# ADC_Subsystem.net
KiCad netlist of a schematic drawn in Altium Designer
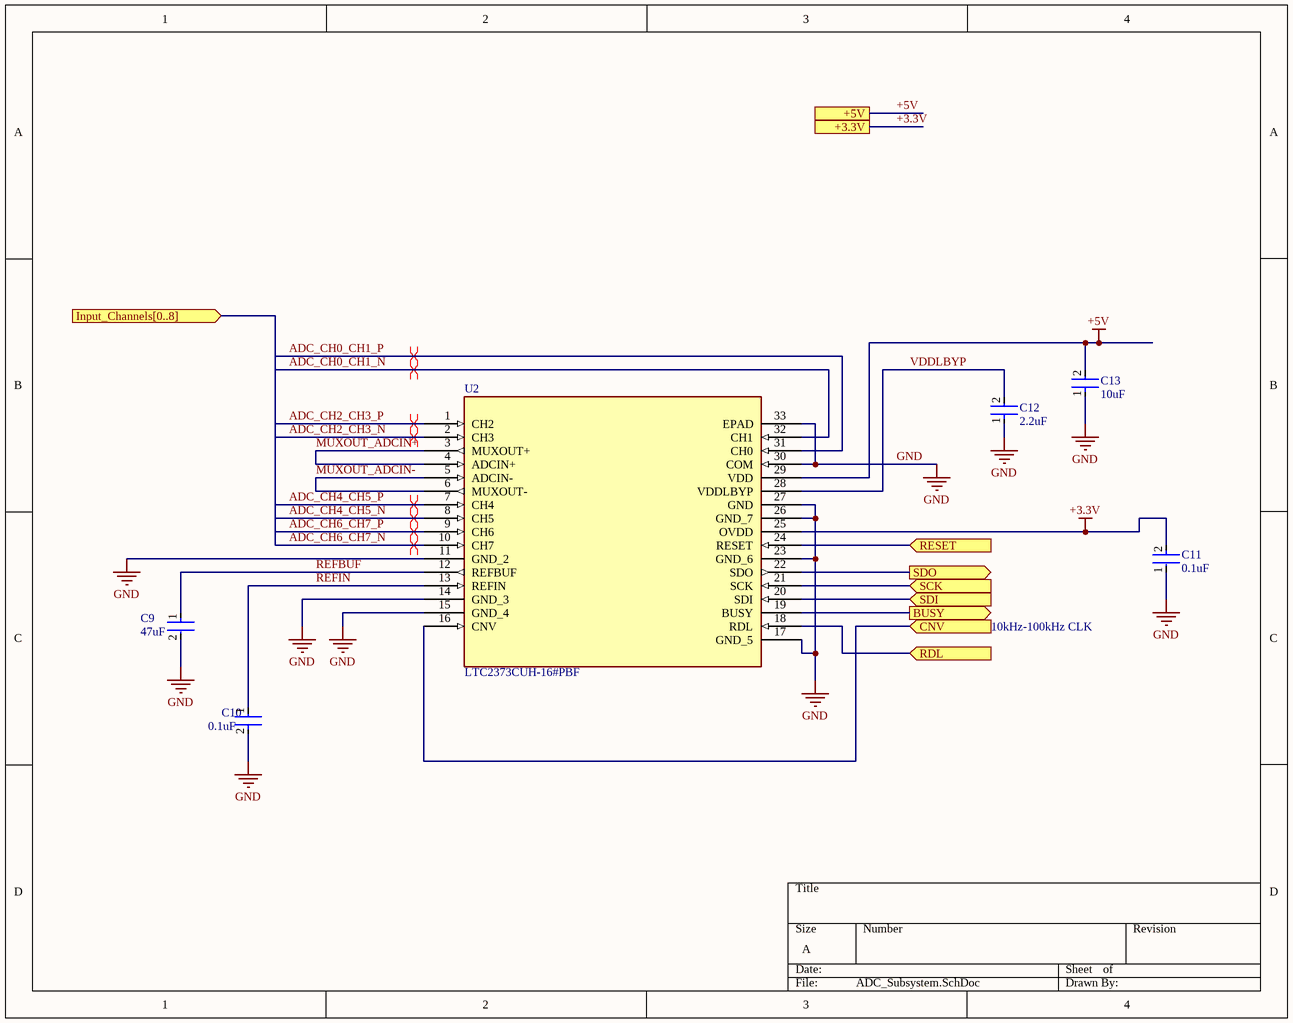
[diagram p0: ADC_Subsystem.SchDoc]

(export (version "E")
  (design (tool "Eeschema 10.0.6"))
  (components
    (comp (ref "C9")
      (value "47uF")
      (footprint "FP-C0805C476M9PACTU-MFG")
      (description "CAP CER 47UF 6.3V X5R 0805\r\nC0805C476M9PACTU")
      (fields (field (name "VOLTAGE") "6.3V") (field (name "TOLERANCE") "20%"))
      (libsource (lib "Altium Content Vault") (part "11868f565c42a9108669ba33697ecf6"))
    )
    (comp (ref "C10")
      (value "0.1uF")
      (footprint "FP-GRM15-MFG")
      (description "CAP CER 0.1UF 16V X7R 0402\r\nGRM155R71C104KA88D")
      (fields (field (name "MANUFACTURER PART NUMBER") "GRM155R71C104KA88D") (field (name "TOLERANCE") "10%"))
      (libsource (lib "Altium Content Vault") (part "236180d848d6139a670b325ea6854c9"))
    )
    (comp (ref "C11")
      (value "0.1uF")
      (footprint "FP-GRM15-MFG")
      (description "CAP CER 0.1UF 16V X7R 0402\r\nGRM155R71C104KA88D")
      (fields (field (name "MANUFACTURER PART NUMBER") "GRM155R71C104KA88D") (field (name "TOLERANCE") "10%"))
      (libsource (lib "Altium Content Vault") (part "236180d848d6139a670b325ea6854c9"))
    )
    (comp (ref "C12")
      (value "2.2uF")
      (footprint "FP-GRM188-0_1-e0_2_0_5-MFG")
      (fields (field (name "VOLTAGE") "10V") (field (name "TOLERANCE") "10%"))
      (libsource (lib "Altium Content Vault") (part "11868f565c42a9108669ba33697ecf6"))
    )
    (comp (ref "C13")
      (value "10uF")
      (footprint "FP-GRM188-0_1-e0_2_0_55-IPC_A")
      (fields (field (name "VOLTAGE") "6.3V") (field (name "TOLERANCE") "20%"))
      (libsource (lib "Altium Content Vault") (part "02cd4be3c70576c341d710602a673aa"))
    )
    (comp (ref "U2")
      (value "LTC2373CUH-16#PBF")
      (footprint "LTC_2373_Footprint")
      (libsource (lib "LTC2373CUH-16#PBF") (part "LTC2373CUH-16#PBF"))
    )
  )
  (nets
    (net (code "10") (name "+3.3V") (class "Default")
      (node (ref "C11") (pin "2") (pinfunction "2_2") (pintype "passive"))
      (node (ref "U2") (pin "25") (pinfunction "OVDD_25") (pintype "power_in"))
    )
    (net (code "11") (name "+5V") (class "Default")
      (node (ref "C13") (pin "2") (pinfunction "2_2") (pintype "passive"))
      (node (ref "U2") (pin "29") (pinfunction "VDD_29") (pintype "power_in"))
    )
    (net (code "12") (name "/ADC_CH0_CH1_N") (class "Default")
      (node (ref "U2") (pin "32") (pinfunction "CH1_32") (pintype "input"))
    )
    (net (code "13") (name "/ADC_CH0_CH1_P") (class "Default")
      (node (ref "U2") (pin "31") (pinfunction "CH0_31") (pintype "input"))
    )
    (net (code "14") (name "/ADC_CH2_CH3_N") (class "Default")
      (node (ref "U2") (pin "2") (pinfunction "CH3_2") (pintype "input"))
    )
    (net (code "15") (name "/ADC_CH2_CH3_P") (class "Default")
      (node (ref "U2") (pin "1") (pinfunction "CH2_1") (pintype "input"))
    )
    (net (code "16") (name "/ADC_CH4_CH5_N") (class "Default")
      (node (ref "U2") (pin "8") (pinfunction "CH5_8") (pintype "input"))
    )
    (net (code "17") (name "/ADC_CH4_CH5_P") (class "Default")
      (node (ref "U2") (pin "7") (pinfunction "CH4_7") (pintype "input"))
    )
    (net (code "18") (name "/ADC_CH6_CH7_N") (class "Default")
      (node (ref "U2") (pin "10") (pinfunction "CH7_10") (pintype "input"))
    )
    (net (code "19") (name "/ADC_CH6_CH7_P") (class "Default")
      (node (ref "U2") (pin "9") (pinfunction "CH6_9") (pintype "input"))
    )
    (net (code "20") (name "/BUSY") (class "Default")
      (node (ref "U2") (pin "19") (pinfunction "BUSY_19") (pintype "passive"))
    )
    (net (code "21") (name "/CNV") (class "Default")
      (node (ref "U2") (pin "16") (pinfunction "CNV_16") (pintype "input"))
    )
    (net (code "23") (name "/MUXOUT_ADCIN+") (class "Default")
      (node (ref "U2") (pin "3") (pinfunction "MUXOUT+_3") (pintype "output"))
      (node (ref "U2") (pin "4") (pinfunction "ADCIN+_4") (pintype "input"))
    )
    (net (code "24") (name "/MUXOUT_ADCIN-") (class "Default")
      (node (ref "U2") (pin "5") (pinfunction "ADCIN-_5") (pintype "input"))
      (node (ref "U2") (pin "6") (pinfunction "MUXOUT-_6") (pintype "output"))
    )
    (net (code "25") (name "/RDL") (class "Default")
      (node (ref "U2") (pin "18") (pinfunction "RDL_18") (pintype "input"))
    )
    (net (code "26") (name "/REFBUF") (class "Default")
      (node (ref "C9") (pin "1") (pinfunction "1_1") (pintype "passive"))
      (node (ref "U2") (pin "12") (pinfunction "REFBUF_12") (pintype "output"))
    )
    (net (code "27") (name "/REFIN") (class "Default")
      (node (ref "C10") (pin "1") (pinfunction "1_1") (pintype "passive"))
      (node (ref "U2") (pin "13") (pinfunction "REFIN_13") (pintype "input"))
    )
    (net (code "28") (name "/RESET") (class "Default")
      (node (ref "U2") (pin "24") (pinfunction "RESET_24") (pintype "input"))
    )
    (net (code "29") (name "/SCK") (class "Default")
      (node (ref "U2") (pin "21") (pinfunction "SCK_21") (pintype "input"))
    )
    (net (code "30") (name "/SDI") (class "Default")
      (node (ref "U2") (pin "20") (pinfunction "SDI_20") (pintype "input"))
    )
    (net (code "31") (name "/SDO") (class "Default")
      (node (ref "U2") (pin "22") (pinfunction "SDO_22") (pintype "output"))
    )
    (net (code "32") (name "/VDDLBYP") (class "Default")
      (node (ref "C12") (pin "2") (pinfunction "2_2") (pintype "passive"))
      (node (ref "U2") (pin "28") (pinfunction "VDDLBYP_28") (pintype "power_in"))
    )
    (net (code "33") (name "GND") (class "Default")
      (node (ref "C10") (pin "2") (pinfunction "2_2") (pintype "passive"))
      (node (ref "C11") (pin "1") (pinfunction "1_1") (pintype "passive"))
      (node (ref "C12") (pin "1") (pinfunction "1_1") (pintype "passive"))
      (node (ref "C13") (pin "1") (pinfunction "1_1") (pintype "passive"))
      (node (ref "C9") (pin "2") (pinfunction "2_2") (pintype "passive"))
      (node (ref "U2") (pin "11") (pinfunction "GND_2_11") (pintype "power_in"))
      (node (ref "U2") (pin "14") (pinfunction "GND_3_14") (pintype "power_in"))
      (node (ref "U2") (pin "15") (pinfunction "GND_4_15") (pintype "power_in"))
      (node (ref "U2") (pin "17") (pinfunction "GND_5_17") (pintype "power_in"))
      (node (ref "U2") (pin "23") (pinfunction "GND_6_23") (pintype "power_in"))
      (node (ref "U2") (pin "26") (pinfunction "GND_7_26") (pintype "power_in"))
      (node (ref "U2") (pin "27") (pinfunction "GND_27") (pintype "power_in"))
      (node (ref "U2") (pin "30") (pinfunction "COM_30") (pintype "input"))
      (node (ref "U2") (pin "33") (pinfunction "EPAD_33") (pintype "passive"))
    )
  )
)
